# v001.net
KiCad netlist of a schematic drawn in EAGLE
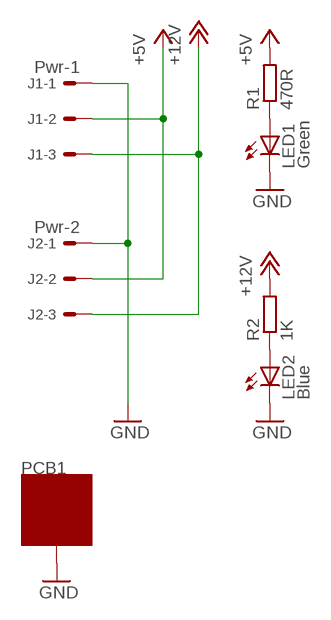
[diagram p0: schematic, sheet 1]

(export (version "E")
  (design (tool "Eeschema 10.0.6"))
  (components
    (comp (ref "J1")
      (value "Pwr-1")
      (footprint "eagle-import:6410-03")
      (libsource (lib "eagle-import") (part "22-?-0327-2031"))
    )
    (comp (ref "J2")
      (value "Pwr-2")
      (footprint "eagle-import:6410-03")
      (libsource (lib "eagle-import") (part "22-?-0327-2031"))
    )
    (comp (ref "LED1")
      (value "Green")
      (footprint "eagle-import:LED3MM")
      (libsource (lib "eagle-import") (part "LED3MM"))
    )
    (comp (ref "LED2")
      (value "Blue")
      (footprint "eagle-import:LED3MM")
      (libsource (lib "eagle-import") (part "LED3MM"))
    )
    (comp (ref "PCB1")
      (value "ZZZ_MODULE05X05")
      (footprint "eagle-import:ZZZ_MODULE_05X05")
      (libsource (lib "eagle-import") (part "ZZZ_MODULE05X05"))
    )
    (comp (ref "R1")
      (value "470R")
      (footprint "eagle-import:0207_2V")
      (libsource (lib "eagle-import") (part "R-EU_0207/2V"))
    )
    (comp (ref "R2")
      (value "1K")
      (footprint "eagle-import:0207_2V")
      (libsource (lib "eagle-import") (part "R-EU_0207/2V"))
    )
  )
  (nets
    (net (code "1") (name "+5V") (class "Default")
      (node (ref "J1") (pin "2") (pinfunction "S_2") (pintype "passive"))
      (node (ref "J2") (pin "2") (pinfunction "S_2") (pintype "passive"))
      (node (ref "R1") (pin "2") (pinfunction "2_2") (pintype "passive"))
    )
    (net (code "2") (name "+12V") (class "Default")
      (node (ref "J1") (pin "3") (pinfunction "S_3") (pintype "passive"))
      (node (ref "J2") (pin "3") (pinfunction "S_3") (pintype "passive"))
      (node (ref "R2") (pin "2") (pinfunction "2_2") (pintype "passive"))
    )
    (net (code "3") (name "GND") (class "Default")
      (node (ref "J1") (pin "1") (pinfunction "S_1") (pintype "passive"))
      (node (ref "J2") (pin "1") (pinfunction "S_1") (pintype "passive"))
      (node (ref "LED1") (pin "K") (pinfunction "C_K") (pintype "passive"))
      (node (ref "LED2") (pin "K") (pinfunction "C_K") (pintype "passive"))
      (node (ref "PCB1") (pin "GND@1") (pinfunction "GND_GND@1") (pintype "power_in"))
      (node (ref "PCB1") (pin "GND@2") (pinfunction "GND_GND@2") (pintype "power_in"))
      (node (ref "PCB1") (pin "GND@3") (pinfunction "GND_GND@3") (pintype "power_in"))
      (node (ref "PCB1") (pin "GND@4") (pinfunction "GND_GND@4") (pintype "power_in"))
      (node (ref "PCB1") (pin "GND@5") (pinfunction "GND_GND@5") (pintype "power_in"))
      (node (ref "PCB1") (pin "GND@6") (pinfunction "GND_GND@6") (pintype "power_in"))
      (node (ref "PCB1") (pin "GND@7") (pinfunction "GND_GND@7") (pintype "power_in"))
      (node (ref "PCB1") (pin "GND@8") (pinfunction "GND_GND@8") (pintype "power_in"))
    )
    (net (code "4") (name "Net-(LED1-PadA)") (class "Default")
      (node (ref "LED1") (pin "A") (pinfunction "A_A") (pintype "passive"))
      (node (ref "R1") (pin "1") (pinfunction "1_1") (pintype "passive"))
    )
    (net (code "5") (name "Net-(LED2-PadA)") (class "Default")
      (node (ref "LED2") (pin "A") (pinfunction "A_A") (pintype "passive"))
      (node (ref "R2") (pin "1") (pinfunction "1_1") (pintype "passive"))
    )
  )
)
